# KEY.net
KiCad netlist of a schematic drawn in Altium Designer
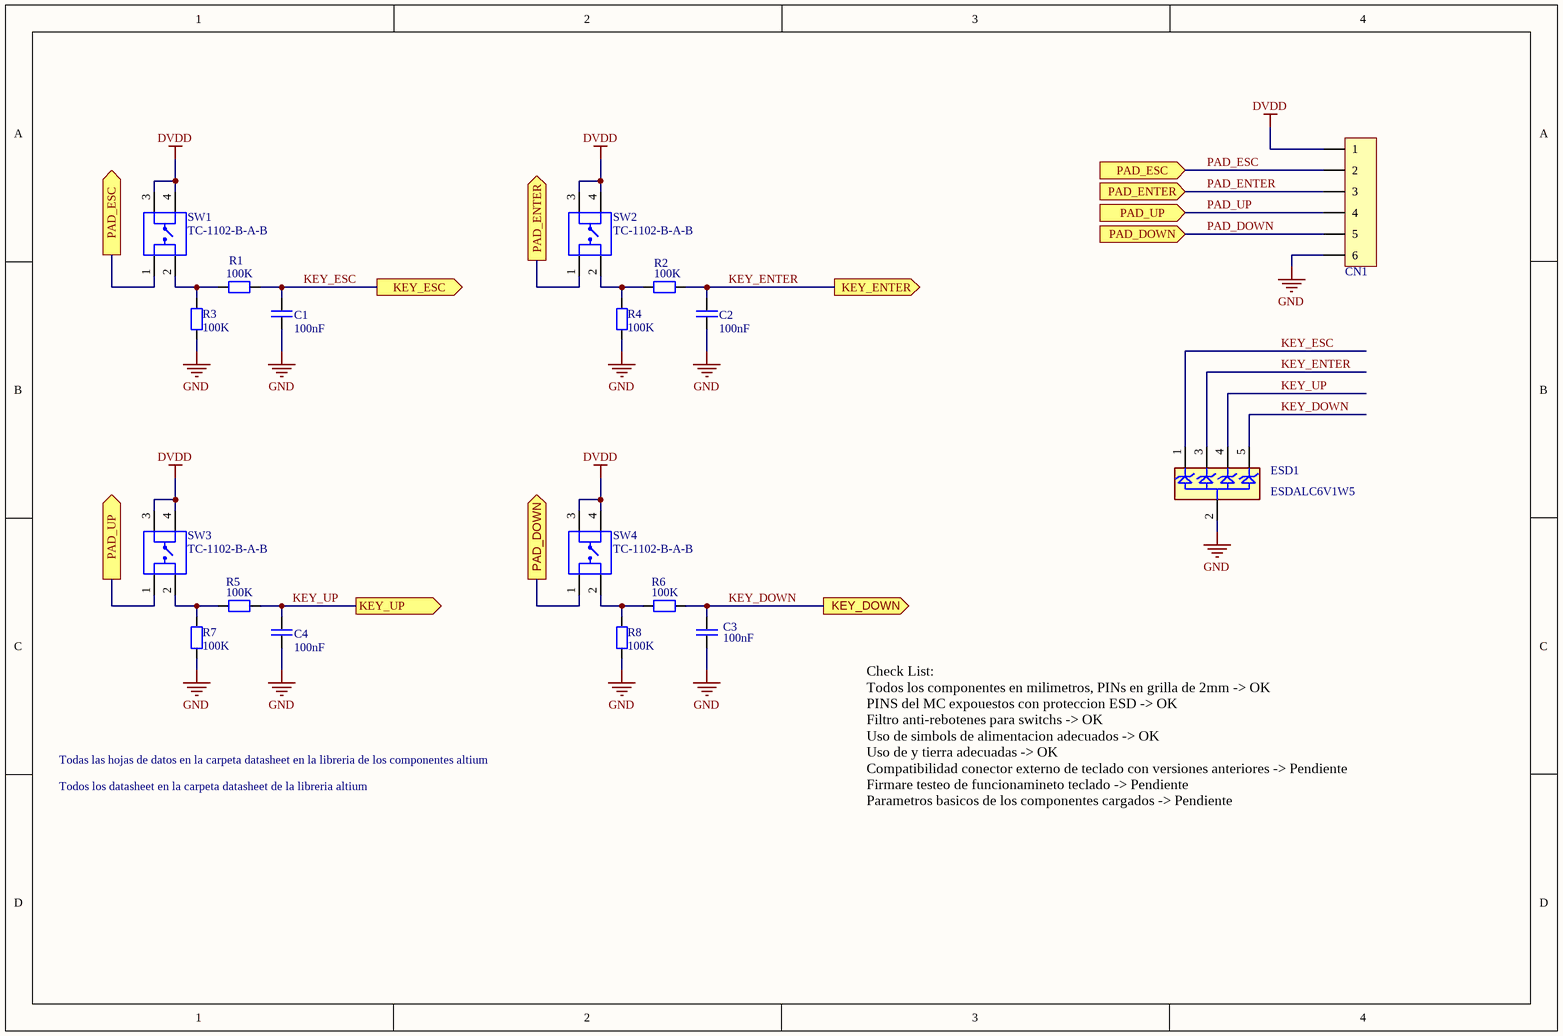
[diagram p0: KEY.SchDoc]

(export (version "E")
  (design (tool "Eeschema 10.0.6"))
  (components
    (comp (ref "C1")
      (value "100nF")
      (footprint "CAP_SM0805_YAGEOCC2_N")
      (description "CAP 100nF SM0805 X7R 25V YAGEO CC2")
      (fields
        (field (name "MANUFACTURER") "Yageo")
        (field (name "MANUFACTURER PART NUMBER") "CC0805KRX7R8BB104")
      )
      (libsource (lib "Yageo") (part "CC0805KRX7R8BB104"))
    )
    (comp (ref "C2")
      (value "100nF")
      (footprint "CAP_SM0805_YAGEOCC2_N")
      (description "CAP 100nF SM0805 X7R 25V YAGEO CC2")
      (fields
        (field (name "MANUFACTURER") "Yageo")
        (field (name "MANUFACTURER PART NUMBER") "CC0805KRX7R8BB104")
      )
      (libsource (lib "Yageo") (part "CC0805KRX7R8BB104"))
    )
    (comp (ref "C3")
      (value "100nF")
      (footprint "CAP_SM0805_YAGEOCC2_N")
      (description "CAP 100nF SM0805 X7R 25V YAGEO CC2")
      (fields
        (field (name "MANUFACTURER") "Yageo")
        (field (name "MANUFACTURER PART NUMBER") "CC0805KRX7R8BB104")
      )
      (libsource (lib "Yageo") (part "CC0805KRX7R8BB104"))
    )
    (comp (ref "C4")
      (value "100nF")
      (footprint "CAP_SM0805_YAGEOCC2_N")
      (description "CAP 100nF SM0805 X7R 25V YAGEO CC2")
      (fields
        (field (name "MANUFACTURER") "Yageo")
        (field (name "MANUFACTURER PART NUMBER") "CC0805KRX7R8BB104")
      )
      (libsource (lib "Yageo") (part "CC0805KRX7R8BB104"))
    )
    (comp (ref "CN1")
      (value "PH2.54-07-06PWD")
      (footprint "HEADER PIN 1X6 A 90 GRADOS")
      (description "1 x 6 - true hole  2.54mm - Pb free - 90°")
      (fields (field (name "MANUFACTURER") "XUNPU"))
      (libsource (lib "header_pin") (part "PH2.54-07-06PWD"))
    )
    (comp (ref "ESD1")
      (value "ESDALC6V1W5")
      (footprint "ESDALC6V1W5")
      (fields (field (name "MANUFACTURER") "ST"))
      (libsource (lib "diode") (part "ESDALC6V1W5"))
    )
    (comp (ref "R1")
      (value "100K")
      (footprint "RES_SM0805_YAGEORC_N")
      (description "RES 100K SM0805 YAGEO RC_L")
      (fields
        (field (name "MANUFACTURER") "Yageo")
        (field (name "MANUFACTURER PART NUMBER") "RC0805FR-07100KL")
      )
      (libsource (lib "Yageo") (part "RC0805FR-07100KL"))
    )
    (comp (ref "R2")
      (value "100K")
      (footprint "RES_SM0805_YAGEORC_N")
      (description "RES 100K SM0805 YAGEO RC_L")
      (fields
        (field (name "MANUFACTURER") "Yageo")
        (field (name "MANUFACTURER PART NUMBER") "RC0805FR-07100KL")
      )
      (libsource (lib "Yageo") (part "RC0805FR-07100KL"))
    )
    (comp (ref "R3")
      (value "100K")
      (footprint "RES_SM0805_YAGEORC_N")
      (description "RES 100K SM0805 YAGEO RC_L")
      (fields
        (field (name "MANUFACTURER") "Yageo")
        (field (name "MANUFACTURER PART NUMBER") "RC0805FR-07100KL")
      )
      (libsource (lib "") (part "RC0805FR-07100KL_1"))
    )
    (comp (ref "R4")
      (value "100K")
      (footprint "RES_SM0805_YAGEORC_N")
      (description "RES 100K SM0805 YAGEO RC_L")
      (fields
        (field (name "MANUFACTURER") "Yageo")
        (field (name "MANUFACTURER PART NUMBER") "RC0805FR-07100KL")
      )
      (libsource (lib "") (part "RC0805FR-07100KL_1"))
    )
    (comp (ref "R5")
      (value "100K")
      (footprint "RES_SM0805_YAGEORC_N")
      (description "RES 100K SM0805 YAGEO RC_L")
      (fields
        (field (name "MANUFACTURER") "Yageo")
        (field (name "MANUFACTURER PART NUMBER") "RC0805FR-07100KL")
      )
      (libsource (lib "Yageo") (part "RC0805FR-07100KL"))
    )
    (comp (ref "R6")
      (value "100K")
      (footprint "RES_SM0805_YAGEORC_N")
      (description "RES 100K SM0805 YAGEO RC_L")
      (fields
        (field (name "MANUFACTURER") "Yageo")
        (field (name "MANUFACTURER PART NUMBER") "RC0805FR-07100KL")
      )
      (libsource (lib "Yageo") (part "RC0805FR-07100KL"))
    )
    (comp (ref "R7")
      (value "100K")
      (footprint "RES_SM0805_YAGEORC_N")
      (description "RES 100K SM0805 YAGEO RC_L")
      (fields
        (field (name "MANUFACTURER") "Yageo")
        (field (name "MANUFACTURER PART NUMBER") "RC0805FR-07100KL")
      )
      (libsource (lib "") (part "RC0805FR-07100KL_1"))
    )
    (comp (ref "R8")
      (value "100K")
      (footprint "RES_SM0805_YAGEORC_N")
      (description "RES 100K SM0805 YAGEO RC_L")
      (fields
        (field (name "MANUFACTURER") "Yageo")
        (field (name "MANUFACTURER PART NUMBER") "RC0805FR-07100KL")
      )
      (libsource (lib "") (part "RC0805FR-07100KL_1"))
    )
    (comp (ref "SW1")
      (value "TC-1102-B-A-B")
      (footprint "TC-1102-B-A-B")
      (description "Switch tactile 6x6mm true hole.")
      (fields (field (name "MANUFACTURER") "XKB Connectivity"))
      (libsource (lib "Switches") (part "TC-1102-B-A-B"))
    )
    (comp (ref "SW2")
      (value "TC-1102-B-A-B")
      (footprint "TC-1102-B-A-B")
      (description "Switch tactile 6x6mm true hole.")
      (fields (field (name "MANUFACTURER") "XKB Connectivity"))
      (libsource (lib "Switches") (part "TC-1102-B-A-B"))
    )
    (comp (ref "SW3")
      (value "TC-1102-B-A-B")
      (footprint "TC-1102-B-A-B")
      (description "Switch tactile 6x6mm true hole.")
      (fields (field (name "MANUFACTURER") "XKB Connectivity"))
      (libsource (lib "Switches") (part "TC-1102-B-A-B"))
    )
    (comp (ref "SW4")
      (value "TC-1102-B-A-B")
      (footprint "TC-1102-B-A-B")
      (description "Switch tactile 6x6mm true hole.")
      (fields (field (name "MANUFACTURER") "XKB Connectivity"))
      (libsource (lib "Switches") (part "TC-1102-B-A-B"))
    )
  )
  (nets
    (net (code "1") (name "/KEY_DOWN") (class "Default")
      (node (ref "C3") (pin "1") (pintype "passive"))
      (node (ref "ESD1") (pin "5") (pinfunction "I/04_5") (pintype "passive"))
      (node (ref "R6") (pin "2") (pintype "passive"))
    )
    (net (code "2") (name "/KEY_ENTER") (class "Default")
      (node (ref "C2") (pin "1") (pintype "passive"))
      (node (ref "ESD1") (pin "3") (pinfunction "I/02_3") (pintype "passive"))
      (node (ref "R2") (pin "2") (pintype "passive"))
    )
    (net (code "3") (name "/KEY_ESC") (class "Default")
      (node (ref "C1") (pin "1") (pintype "passive"))
      (node (ref "ESD1") (pin "1") (pinfunction "I/01_1") (pintype "passive"))
      (node (ref "R1") (pin "2") (pintype "passive"))
    )
    (net (code "4") (name "/KEY_UP") (class "Default")
      (node (ref "C4") (pin "1") (pintype "passive"))
      (node (ref "ESD1") (pin "4") (pinfunction "I/03_4") (pintype "passive"))
      (node (ref "R5") (pin "2") (pintype "passive"))
    )
    (net (code "5") (name "/PAD_DOWN") (class "Default")
      (node (ref "CN1") (pin "5") (pinfunction "5_5") (pintype "passive"))
      (node (ref "SW4") (pin "1") (pinfunction "1_1") (pintype "passive"))
    )
    (net (code "6") (name "/PAD_ENTER") (class "Default")
      (node (ref "CN1") (pin "3") (pinfunction "3_3") (pintype "passive"))
      (node (ref "SW2") (pin "1") (pinfunction "1_1") (pintype "passive"))
    )
    (net (code "7") (name "/PAD_ESC") (class "Default")
      (node (ref "CN1") (pin "2") (pinfunction "2_2") (pintype "passive"))
      (node (ref "SW1") (pin "1") (pinfunction "1_1") (pintype "passive"))
    )
    (net (code "8") (name "/PAD_UP") (class "Default")
      (node (ref "CN1") (pin "4") (pinfunction "4_4") (pintype "passive"))
      (node (ref "SW3") (pin "1") (pinfunction "1_1") (pintype "passive"))
    )
    (net (code "9") (name "DVDD") (class "Default")
      (node (ref "CN1") (pin "1") (pinfunction "1_1") (pintype "passive"))
      (node (ref "SW1") (pin "3") (pinfunction "g_3") (pintype "passive"))
      (node (ref "SW1") (pin "4") (pinfunction "4_4") (pintype "passive"))
      (node (ref "SW2") (pin "3") (pinfunction "g_3") (pintype "passive"))
      (node (ref "SW2") (pin "4") (pinfunction "4_4") (pintype "passive"))
      (node (ref "SW3") (pin "3") (pinfunction "g_3") (pintype "passive"))
      (node (ref "SW3") (pin "4") (pinfunction "4_4") (pintype "passive"))
      (node (ref "SW4") (pin "3") (pinfunction "g_3") (pintype "passive"))
      (node (ref "SW4") (pin "4") (pinfunction "4_4") (pintype "passive"))
    )
    (net (code "10") (name "GND") (class "Default")
      (node (ref "C1") (pin "2") (pintype "passive"))
      (node (ref "C2") (pin "2") (pintype "passive"))
      (node (ref "C3") (pin "2") (pintype "passive"))
      (node (ref "C4") (pin "2") (pintype "passive"))
      (node (ref "CN1") (pin "6") (pinfunction "6_6") (pintype "passive"))
      (node (ref "ESD1") (pin "2") (pinfunction "GND_2") (pintype "passive"))
      (node (ref "R3") (pin "1") (pintype "passive"))
      (node (ref "R4") (pin "1") (pintype "passive"))
      (node (ref "R7") (pin "1") (pintype "passive"))
      (node (ref "R8") (pin "1") (pintype "passive"))
    )
    (net (code "11") (name "Net-(R1-Pad1)") (class "Default")
      (node (ref "R1") (pin "1") (pintype "passive"))
      (node (ref "R3") (pin "2") (pintype "passive"))
      (node (ref "SW1") (pin "2") (pinfunction "2_2") (pintype "passive"))
    )
    (net (code "12") (name "Net-(R2-Pad1)") (class "Default")
      (node (ref "R2") (pin "1") (pintype "passive"))
      (node (ref "R4") (pin "2") (pintype "passive"))
      (node (ref "SW2") (pin "2") (pinfunction "2_2") (pintype "passive"))
    )
    (net (code "13") (name "Net-(R5-Pad1)") (class "Default")
      (node (ref "R5") (pin "1") (pintype "passive"))
      (node (ref "R7") (pin "2") (pintype "passive"))
      (node (ref "SW3") (pin "2") (pinfunction "2_2") (pintype "passive"))
    )
    (net (code "14") (name "Net-(R6-Pad1)") (class "Default")
      (node (ref "R6") (pin "1") (pintype "passive"))
      (node (ref "R8") (pin "2") (pintype "passive"))
      (node (ref "SW4") (pin "2") (pinfunction "2_2") (pintype "passive"))
    )
  )
)
